# SCH_SaltyMold_2025-03-13.net
KiCad netlist of a schematic drawn in EasyEDA
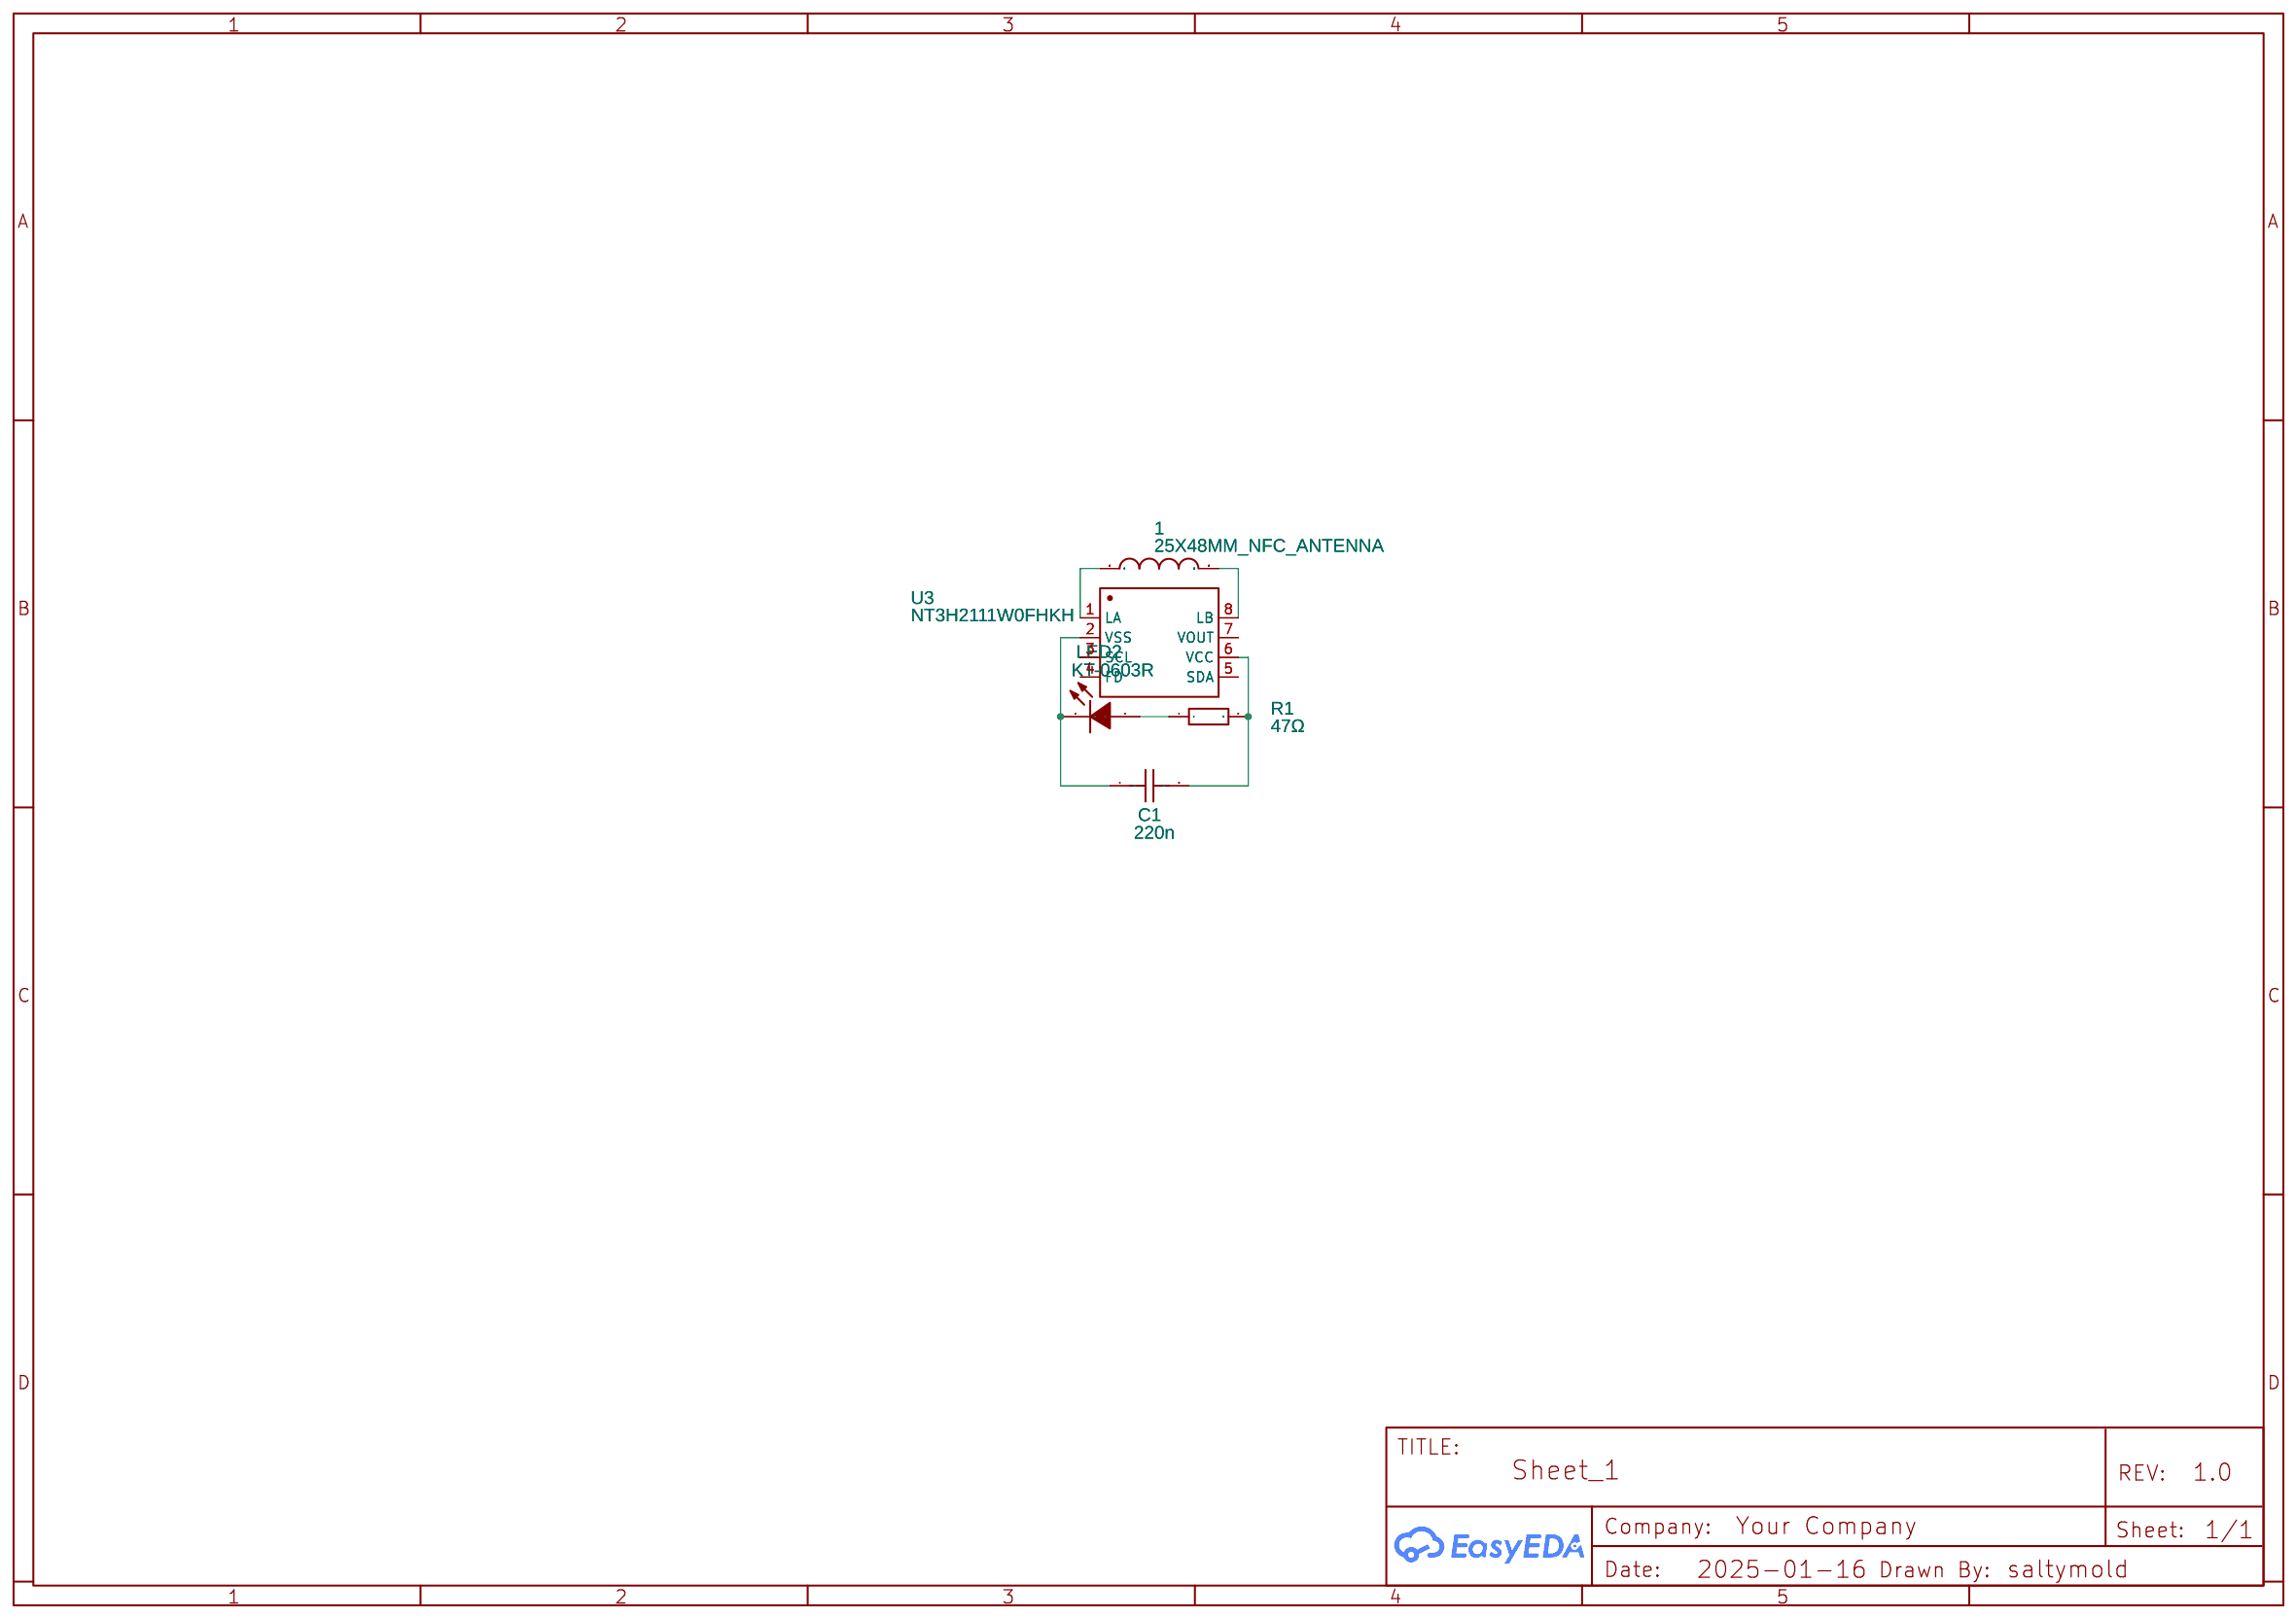
[diagram p0: schematic sheet]

(export (version "E")
  (design (tool "Eeschema 10.0.6"))
  (components
    (comp (ref "1") (value "25X48MM_NFC_ANTENNA") (libsource (lib "") (part "25X48MM_NFC_ANTENNA")))
    (comp (ref "C1") (value "220n") (libsource (lib "") (part "C_0603_US")))
    (comp (ref "LED2")
      (value "KT-0603R")
      (fields (field (name "Manufacturer") "KENTO"))
      (libsource (lib "") (part "KT-0603R"))
    )
    (comp (ref "R1")
      (value "47Ω")
      (fields
        (field (name "Manufacturer Part") "0603WAF470JT5E")
        (field (name "Manufacturer") "UNI-ROYAL(厚声)")
      )
      (libsource (lib "") (part "0603WAF470JT5E"))
    )
    (comp (ref "U3")
      (value "NT3H2111W0FHKH")
      (fields (field (name "Manufacturer") "NXP(恩智浦)"))
      (libsource (lib "") (part "NT3H2111W0FHKH"))
    )
  )
  (nets
    (net (code "1") (name "Net-(LED2-A)") (class "Default")
      (node (ref "LED2") (pin "2") (pinfunction "A_2") (pintype "unspecified"))
      (node (ref "R1") (pin "1") (pinfunction "1_1") (pintype "input"))
    )
    (net (code "2") (name "Net-(LED2-K)") (class "Default")
      (node (ref "C1") (pin "1") (pinfunction "1_1") (pintype "unspecified"))
      (node (ref "LED2") (pin "1") (pinfunction "K_1") (pintype "unspecified"))
      (node (ref "U3") (pin "2") (pinfunction "VSS_2") (pintype "unspecified"))
    )
    (net (code "3") (name "Net-(U3-LA)") (class "Default")
      (node (ref "1") (pin "P$1") (pinfunction "P$1_P$1") (pintype "bidirectional"))
      (node (ref "U3") (pin "1") (pinfunction "LA_1") (pintype "unspecified"))
    )
    (net (code "4") (name "Net-(U3-LB)") (class "Default")
      (node (ref "1") (pin "P$2") (pinfunction "P$2_P$2") (pintype "bidirectional"))
      (node (ref "U3") (pin "8") (pinfunction "LB_8") (pintype "unspecified"))
    )
    (net (code "5") (name "Net-(U3-VCC)") (class "Default")
      (node (ref "C1") (pin "2") (pinfunction "2_2") (pintype "unspecified"))
      (node (ref "R1") (pin "2") (pinfunction "2_2") (pintype "input"))
      (node (ref "U3") (pin "6") (pinfunction "VCC_6") (pintype "unspecified"))
    )
    (net (code "6") (name "unconnected-(U3-FD-Pad4)") (class "Default")
      (node (ref "U3") (pin "4") (pinfunction "FD_4") (pintype "unspecified"))
    )
    (net (code "7") (name "unconnected-(U3-SCL-Pad3)") (class "Default")
      (node (ref "U3") (pin "3") (pinfunction "SCL_3") (pintype "unspecified"))
    )
    (net (code "8") (name "unconnected-(U3-SDA-Pad5)") (class "Default")
      (node (ref "U3") (pin "5") (pinfunction "SDA_5") (pintype "unspecified"))
    )
    (net (code "9") (name "unconnected-(U3-VOUT-Pad7)") (class "Default")
      (node (ref "U3") (pin "7") (pinfunction "VOUT_7") (pintype "unspecified"))
    )
  )
)
